# RECOM_24to3v3.net
KiCad netlist of a schematic drawn in Altium Designer
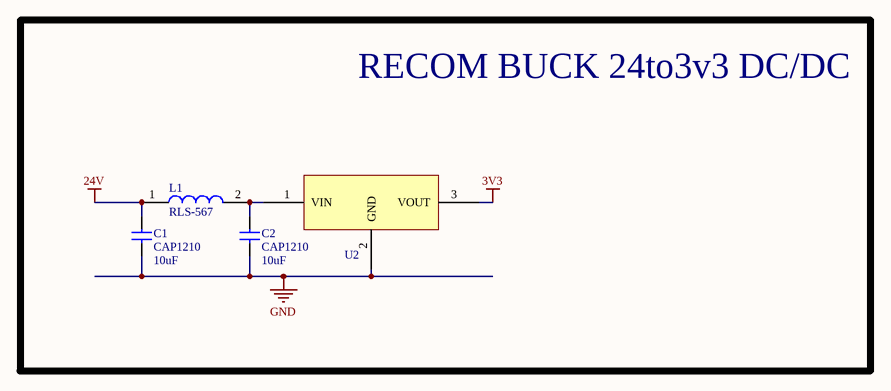
[diagram p0: RECOM_24to3v3.SchDoc]

(export (version "E")
  (design (tool "Eeschema 10.0.6"))
  (components
    (comp (ref "C1")
      (value "CAP1210")
      (footprint "CAP1210")
      (description "CAP CER 10UF 50V 20% X5R 1210")
      (fields (field (name "ALTIUM_VALUE") "10uF"))
      (libsource (lib "SubjuGator8") (part "CAP1210"))
    )
    (comp (ref "C2")
      (value "CAP1210")
      (footprint "CAP1210")
      (description "CAP CER 10UF 50V 20% X5R 1210")
      (fields (field (name "ALTIUM_VALUE") "10uF"))
      (libsource (lib "SubjuGator8") (part "CAP1210"))
    )
    (comp (ref "L1")
      (value "RLS-567")
      (footprint "RLS567")
      (description "Inductor")
      (fields (field (name "MOUSER PART NUMBER") "919-RLS-567"))
      (libsource (lib "SubjuGator8") (part "RLS-567"))
    )
    (comp (ref "U2")
      (value "R-78C3.3-1.0")
      (footprint "R-78C3.3-1.0")
      (description "CONV DC/DC 1A 3.3V OUT SIP VERT")
      (libsource (lib "SubjuGator8") (part "R-78C3.3-1.0"))
    )
  )
  (nets
    (net (code "1") (name "3V3") (class "Default")
      (node (ref "U2") (pin "3") (pinfunction "VOUT_3") (pintype "passive"))
    )
    (net (code "2") (name "24V") (class "Default")
      (node (ref "C1") (pin "1") (pinfunction "A_1") (pintype "passive"))
      (node (ref "L1") (pin "1") (pinfunction "1_1") (pintype "passive"))
    )
    (net (code "3") (name "GND") (class "Default")
      (node (ref "C1") (pin "2") (pinfunction "B_2") (pintype "passive"))
      (node (ref "C2") (pin "2") (pinfunction "B_2") (pintype "passive"))
      (node (ref "U2") (pin "2") (pinfunction "GND_2") (pintype "power_in"))
    )
    (net (code "4") (name "Net-(C2-A)") (class "Default")
      (node (ref "C2") (pin "1") (pinfunction "A_1") (pintype "passive"))
      (node (ref "L1") (pin "2") (pinfunction "2_2") (pintype "passive"))
      (node (ref "U2") (pin "1") (pinfunction "VIN_1") (pintype "passive"))
    )
  )
)
